# CONTROL_BOARD_V2.net
KiCad netlist of a schematic drawn in Altium Designer
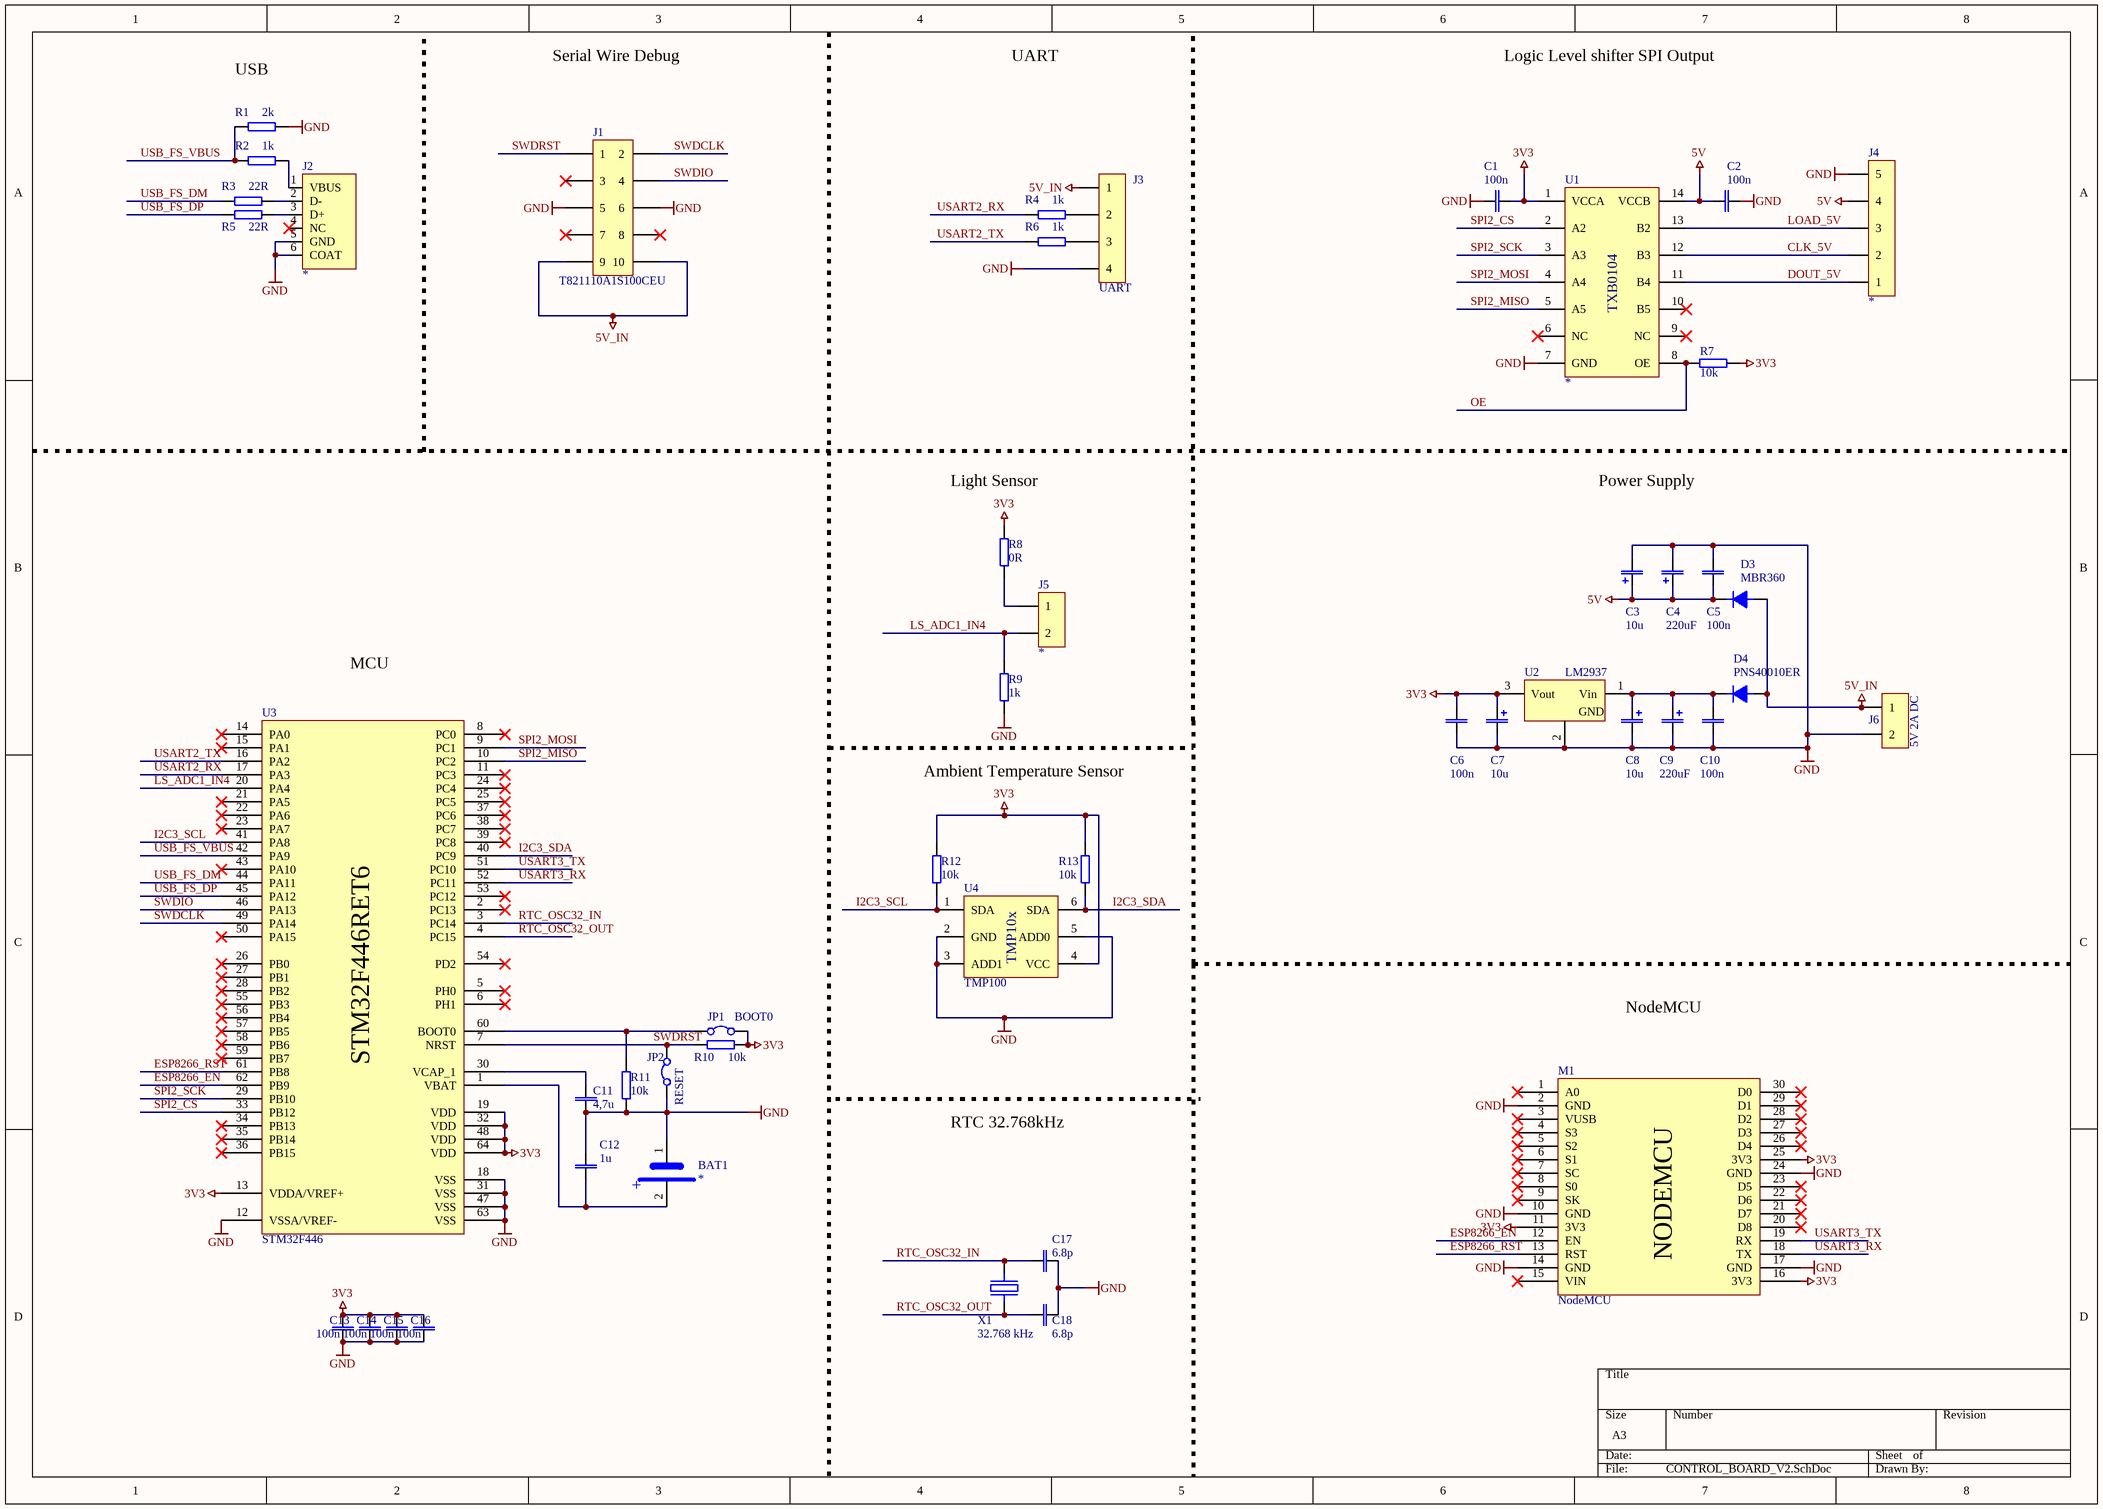
[diagram p0: CONTROL_BOARD_V2.SchDoc]

(export (version "E")
  (design (tool "Eeschema 10.0.6"))
  (components
    (comp (ref "BAT1")
      (value "*")
      (footprint "CR2032")
      (description "battery")
      (libsource (lib "SCH_LIB") (part "Battery"))
    )
    (comp (ref "C1")
      (value "100n")
      (footprint "CAP 0805")
      (description "NON POLARIZED CAPACITOR")
      (libsource (lib "SCH_LIB") (part "CAP"))
    )
    (comp (ref "C2")
      (value "100n")
      (footprint "CAP 0805")
      (description "NON POLARIZED CAPACITOR")
      (libsource (lib "SCH_LIB") (part "CAP"))
    )
    (comp (ref "C3")
      (value "10u")
      (footprint "CAP 1210")
      (description "POLARIZED CAPACITOR")
      (libsource (lib "SCH_LIB") (part "CAP_POL"))
    )
    (comp (ref "C4")
      (value "220uF")
      (footprint "G ELKO")
      (description "POLARIZED CAPACITOR")
      (libsource (lib "SCH_LIB") (part "CAP_POL"))
    )
    (comp (ref "C5")
      (value "100n")
      (footprint "CAP 0805")
      (description "NON POLARIZED CAPACITOR")
      (libsource (lib "SCH_LIB") (part "CAP"))
    )
    (comp (ref "C6")
      (value "100n")
      (footprint "CAP 0805")
      (description "NON POLARIZED CAPACITOR")
      (libsource (lib "SCH_LIB") (part "CAP"))
    )
    (comp (ref "C7")
      (value "10u")
      (footprint "CAP 1210")
      (description "POLARIZED CAPACITOR")
      (libsource (lib "SCH_LIB") (part "CAP_POL"))
    )
    (comp (ref "C8")
      (value "10u")
      (footprint "CAP 1210")
      (description "POLARIZED CAPACITOR")
      (libsource (lib "SCH_LIB") (part "CAP_POL"))
    )
    (comp (ref "C9")
      (value "220uF")
      (footprint "G ELKO")
      (description "POLARIZED CAPACITOR")
      (libsource (lib "SCH_LIB") (part "CAP_POL"))
    )
    (comp (ref "C10")
      (value "100n")
      (footprint "CAP 0805")
      (description "NON POLARIZED CAPACITOR")
      (libsource (lib "SCH_LIB") (part "CAP"))
    )
    (comp (ref "C11")
      (value "4,7u")
      (footprint "CAP 0805")
      (description "NON POLARIZED CAPACITOR")
      (libsource (lib "SCH_LIB") (part "CAP"))
    )
    (comp (ref "C12")
      (value "1u")
      (footprint "CAP 0805")
      (description "NON POLARIZED CAPACITOR")
      (libsource (lib "SCH_LIB") (part "CAP"))
    )
    (comp (ref "C13")
      (value "100n")
      (footprint "CAP 0805")
      (description "NON POLARIZED CAPACITOR")
      (libsource (lib "SCH_LIB") (part "CAP"))
    )
    (comp (ref "C14")
      (value "100n")
      (footprint "CAP 0805")
      (description "NON POLARIZED CAPACITOR")
      (libsource (lib "SCH_LIB") (part "CAP"))
    )
    (comp (ref "C15")
      (value "100n")
      (footprint "CAP 0805")
      (description "NON POLARIZED CAPACITOR")
      (libsource (lib "SCH_LIB") (part "CAP"))
    )
    (comp (ref "C16")
      (value "100n")
      (footprint "CAP 0805")
      (description "NON POLARIZED CAPACITOR")
      (libsource (lib "SCH_LIB") (part "CAP"))
    )
    (comp (ref "C17")
      (value "6.8p")
      (footprint "CAP 0805")
      (description "NON POLARIZED CAPACITOR")
      (libsource (lib "SCH_LIB") (part "CAP"))
    )
    (comp (ref "C18")
      (value "6.8p")
      (footprint "CAP 0805")
      (description "NON POLARIZED CAPACITOR")
      (libsource (lib "SCH_LIB") (part "CAP"))
    )
    (comp (ref "D3")
      (value "MBR360")
      (footprint "DO-201AD")
      (description "ON Semiconductor MBR360,SCHOTTKY BARRIER RECTIFIERS\r\n3.0 AMPERES 60 VOLTS")
      (fields (field (name "MANUFACTURER") "ON Semiconductor"))
      (libsource (lib "SCH_LIB") (part "MBR360"))
    )
    (comp (ref "D4")
      (value "PNS40010ER")
      (footprint "SOD-123")
      (description "Nexperia PNS40010ER,115 switching diode 1.4A, 400V, SOD-123")
      (fields (field (name "MANUFACTURER") "Nexperia"))
      (libsource (lib "SCH_LIB") (part "PNS40010ER"))
    )
    (comp (ref "J1")
      (value "T821110A1S100CEU")
      (footprint "MLW10")
      (description "T821, 10pin, 2x5 connector, 2.54mm")
      (fields (field (name "MANUFACTURER") "Amphenol"))
      (libsource (lib "SCH_LIB") (part "T821-10"))
    )
    (comp (ref "J2")
      (value "*")
      (footprint "MUSB-B2.0S05PFHSB-T")
      (description "5PIN miniUSB SMD connector")
      (libsource (lib "SCH_LIB") (part "USB_5PIN"))
    )
    (comp (ref "J3")
      (value "UART")
      (footprint "SIL4")
      (description "4 PIN HEADER")
      (libsource (lib "SCH_LIB") (part "HEADER4"))
    )
    (comp (ref "J4")
      (value "*")
      (footprint "SIL5")
      (description "5 PIN HEADER")
      (libsource (lib "SCH_LIB") (part "HEADER5"))
    )
    (comp (ref "J5")
      (value "*")
      (footprint "SIL2")
      (description "2 PIN HEADER")
      (libsource (lib "SCH_LIB") (part "HEADER2"))
    )
    (comp (ref "J6")
      (value "5V 2A DC")
      (footprint "PTR_AKZ350")
      (description "2 Pin Terminal Block")
      (fields (field (name "MANUFACTURER") "TE Connectivity"))
      (libsource (lib "SCH_LIB") (part "TB-2"))
    )
    (comp (ref "JP1")
      (value "BOOT0")
      (footprint "SIL2")
      (description "JUMPER")
      (libsource (lib "SCH_LIB") (part "JUMPER"))
    )
    (comp (ref "JP2")
      (value "RESET")
      (footprint "SIL2")
      (description "JUMPER")
      (libsource (lib "SCH_LIB") (part "JUMPER"))
    )
    (comp (ref "M1")
      (value "NodeMCU")
      (footprint "NodeMcu")
      (description "Node MCU ESP12 module")
      (libsource (lib "SCH_LIB") (part "NodeMCU"))
    )
    (comp (ref "R1")
      (value "2k")
      (footprint "RES 0805")
      (description "RESISTOR")
      (libsource (lib "SCH_LIB") (part "RES"))
    )
    (comp (ref "R2")
      (value "1k")
      (footprint "RES 0805")
      (description "RESISTOR")
      (libsource (lib "SCH_LIB") (part "RES"))
    )
    (comp (ref "R3")
      (value "22R")
      (footprint "RES 0805")
      (description "RESISTOR")
      (libsource (lib "SCH_LIB") (part "RES"))
    )
    (comp (ref "R4")
      (value "1k")
      (footprint "RES 0805")
      (description "RESISTOR")
      (libsource (lib "SCH_LIB") (part "RES"))
    )
    (comp (ref "R5")
      (value "22R")
      (footprint "RES 0805")
      (description "RESISTOR")
      (libsource (lib "SCH_LIB") (part "RES"))
    )
    (comp (ref "R6")
      (value "1k")
      (footprint "RES 0805")
      (description "RESISTOR")
      (libsource (lib "SCH_LIB") (part "RES"))
    )
    (comp (ref "R7")
      (value "10k")
      (footprint "RES 0805")
      (description "RESISTOR")
      (libsource (lib "SCH_LIB") (part "RES"))
    )
    (comp (ref "R8")
      (value "0R")
      (footprint "RES 0805")
      (description "RESISTOR")
      (libsource (lib "") (part "RES_2"))
    )
    (comp (ref "R9")
      (value "1k")
      (footprint "RES 0805")
      (description "RESISTOR")
      (libsource (lib "") (part "RES_2"))
    )
    (comp (ref "R10")
      (value "10k")
      (footprint "RES 0805")
      (description "RESISTOR")
      (libsource (lib "") (part "RES_3"))
    )
    (comp (ref "R11")
      (value "10k")
      (footprint "RES 0805")
      (description "RESISTOR")
      (libsource (lib "") (part "RES_1"))
    )
    (comp (ref "R12")
      (value "10k")
      (footprint "RES 0805")
      (description "RESISTOR")
      (libsource (lib "") (part "RES_1"))
    )
    (comp (ref "R13")
      (value "10k")
      (footprint "RES 0805")
      (description "RESISTOR")
      (libsource (lib "") (part "RES_1"))
    )
    (comp (ref "U1")
      (value "*")
      (footprint "SO14")
      (description "Voltage level shifter")
      (libsource (lib "SCH_LIB") (part "TXB0104"))
    )
    (comp (ref "U2")
      (value "LM2937")
      (footprint "SOT223")
      (description "LDO-regulator 400mA 3,3 V 5%, 4,75 → 26 V, SOT223")
      (fields (field (name "MANUFACTURER") "Texas Instruments"))
      (libsource (lib "SCH_LIB") (part "LM2937"))
    )
    (comp (ref "U3")
      (value "STM32F446")
      (footprint "LQFP64")
      (description "MCU STM32F446RET6 32bit, ARM Cortex M4, 180MHz, Flash, 128 kB RAM, 2xUSB USB, LQFP-64")
      (fields (field (name "MANUFACTURER") "ST Microelectronics"))
      (libsource (lib "SCH_LIB") (part "STM32F446RET6"))
    )
    (comp (ref "U4")
      (value "TMP100")
      (footprint "SOT-23-6L")
      (description "Temperature sensor with I2C interface")
      (fields (field (name "MANUFACTURER") "Texas Instruments"))
      (libsource (lib "SCH_LIB") (part "TMP10x"))
    )
    (comp (ref "X1")
      (value "32.768 kHz")
      (footprint "X32K768L104")
      (description "Crystal, 32.768 kHz, Cylinder Radial, 8mm x 3mm Dia, 12.5 pF, 20 ppm")
      (fields (field (name "MANUFACTURER") "AEL CRYSTALS"))
      (libsource (lib "SCH_LIB") (part "X32K768L104"))
    )
  )
  (nets
    (net (code "1") (name "/CLK_5V") (class "Default")
      (node (ref "J4") (pin "2") (pinfunction "2_2") (pintype "passive"))
      (node (ref "U1") (pin "12") (pinfunction "B3_12") (pintype "passive"))
    )
    (net (code "2") (name "/DOUT_5V") (class "Default")
      (node (ref "J4") (pin "1") (pinfunction "1_1") (pintype "passive"))
      (node (ref "U1") (pin "11") (pinfunction "B4_11") (pintype "passive"))
    )
    (net (code "3") (name "/ESP8266_EN") (class "Default")
      (node (ref "M1") (pin "12") (pinfunction "EN_12") (pintype "passive"))
      (node (ref "U3") (pin "62") (pinfunction "PB9_62") (pintype "passive"))
    )
    (net (code "4") (name "/ESP8266_RST") (class "Default")
      (node (ref "M1") (pin "13") (pinfunction "RST_13") (pintype "passive"))
      (node (ref "U3") (pin "61") (pinfunction "PB8_61") (pintype "passive"))
    )
    (net (code "5") (name "/I2C3_SCL") (class "Default")
      (node (ref "R12") (pin "1") (pinfunction "1_1") (pintype "passive"))
      (node (ref "U3") (pin "41") (pinfunction "PA8_41") (pintype "passive"))
      (node (ref "U4") (pin "1") (pinfunction "SDA_1") (pintype "passive"))
    )
    (net (code "6") (name "/I2C3_SDA") (class "Default")
      (node (ref "R13") (pin "1") (pinfunction "1_1") (pintype "passive"))
      (node (ref "U3") (pin "40") (pinfunction "PC9_40") (pintype "passive"))
      (node (ref "U4") (pin "6") (pinfunction "SDA_6") (pintype "passive"))
    )
    (net (code "7") (name "/LOAD_5V") (class "Default")
      (node (ref "J4") (pin "3") (pinfunction "3_3") (pintype "passive"))
      (node (ref "U1") (pin "13") (pinfunction "B2_13") (pintype "passive"))
    )
    (net (code "8") (name "/LS_ADC1_IN4") (class "Default")
      (node (ref "J5") (pin "2") (pinfunction "2_2") (pintype "passive"))
      (node (ref "R9") (pin "1") (pinfunction "1_1") (pintype "passive"))
      (node (ref "U3") (pin "20") (pinfunction "PA4_20") (pintype "passive"))
    )
    (net (code "9") (name "/OE") (class "Default")
      (node (ref "R7") (pin "2") (pinfunction "2_2") (pintype "passive"))
      (node (ref "U1") (pin "8") (pinfunction "OE_8") (pintype "passive"))
    )
    (net (code "10") (name "/RTC_OSC32_IN") (class "Default")
      (node (ref "C17") (pin "2") (pinfunction "2_2") (pintype "passive"))
      (node (ref "U3") (pin "3") (pinfunction "PC14_3") (pintype "passive"))
      (node (ref "X1") (pin "2") (pinfunction "GND_2") (pintype "passive"))
    )
    (net (code "11") (name "/RTC_OSC32_OUT") (class "Default")
      (node (ref "C18") (pin "2") (pinfunction "2_2") (pintype "passive"))
      (node (ref "U3") (pin "4") (pinfunction "PC15_4") (pintype "passive"))
      (node (ref "X1") (pin "1") (pinfunction "1_1") (pintype "passive"))
    )
    (net (code "12") (name "/SPI2_CS") (class "Default")
      (node (ref "U1") (pin "2") (pinfunction "A2_2") (pintype "passive"))
      (node (ref "U3") (pin "33") (pinfunction "PB12_33") (pintype "passive"))
    )
    (net (code "13") (name "/SPI2_MISO") (class "Default")
      (node (ref "U1") (pin "5") (pinfunction "A5_5") (pintype "passive"))
      (node (ref "U3") (pin "10") (pinfunction "PC2_10") (pintype "passive"))
    )
    (net (code "14") (name "/SPI2_MOSI") (class "Default")
      (node (ref "U1") (pin "4") (pinfunction "A4_4") (pintype "passive"))
      (node (ref "U3") (pin "9") (pinfunction "PC1_9") (pintype "passive"))
    )
    (net (code "15") (name "/SPI2_SCK") (class "Default")
      (node (ref "U1") (pin "3") (pinfunction "A3_3") (pintype "passive"))
      (node (ref "U3") (pin "29") (pinfunction "PB10_29") (pintype "passive"))
    )
    (net (code "16") (name "/SWDCLK") (class "Default")
      (node (ref "J1") (pin "2") (pinfunction "2_2") (pintype "passive"))
      (node (ref "U3") (pin "49") (pinfunction "PA14_49") (pintype "passive"))
    )
    (net (code "17") (name "/SWDIO") (class "Default")
      (node (ref "J1") (pin "4") (pinfunction "4_4") (pintype "passive"))
      (node (ref "U3") (pin "46") (pinfunction "PA13_46") (pintype "passive"))
    )
    (net (code "18") (name "/SWDRST") (class "Default")
      (node (ref "J1") (pin "1") (pinfunction "1_1") (pintype "passive"))
      (node (ref "JP2") (pin "2") (pinfunction "2_2") (pintype "passive"))
      (node (ref "R10") (pin "1") (pinfunction "1_1") (pintype "passive"))
      (node (ref "U3") (pin "7") (pinfunction "NRST_7") (pintype "passive"))
    )
    (net (code "19") (name "/USART2_RX") (class "Default")
      (node (ref "R4") (pin "2") (pinfunction "2_2") (pintype "passive"))
      (node (ref "U3") (pin "17") (pinfunction "PA3_17") (pintype "passive"))
    )
    (net (code "20") (name "/USART2_TX") (class "Default")
      (node (ref "R6") (pin "2") (pinfunction "2_2") (pintype "passive"))
      (node (ref "U3") (pin "16") (pinfunction "PA2_16") (pintype "passive"))
    )
    (net (code "21") (name "/USART3_RX") (class "Default")
      (node (ref "M1") (pin "18") (pinfunction "TX_18") (pintype "passive"))
      (node (ref "U3") (pin "52") (pinfunction "PC11_52") (pintype "passive"))
    )
    (net (code "22") (name "/USART3_TX") (class "Default")
      (node (ref "M1") (pin "19") (pinfunction "RX_19") (pintype "passive"))
      (node (ref "U3") (pin "51") (pinfunction "PC10_51") (pintype "passive"))
    )
    (net (code "23") (name "/USB_FS_DM") (class "Default")
      (node (ref "R3") (pin "2") (pinfunction "2_2") (pintype "passive"))
      (node (ref "U3") (pin "44") (pinfunction "PA11_44") (pintype "passive"))
    )
    (net (code "24") (name "/USB_FS_DP") (class "Default")
      (node (ref "R5") (pin "2") (pinfunction "2_2") (pintype "passive"))
      (node (ref "U3") (pin "45") (pinfunction "PA12_45") (pintype "passive"))
    )
    (net (code "25") (name "/USB_FS_VBUS") (class "Default")
      (node (ref "R1") (pin "2") (pinfunction "2_2") (pintype "passive"))
      (node (ref "R2") (pin "2") (pinfunction "2_2") (pintype "passive"))
      (node (ref "U3") (pin "42") (pinfunction "PA9_42") (pintype "passive"))
    )
    (net (code "26") (name "3V3") (class "Default")
      (node (ref "C1") (pin "2") (pinfunction "2_2") (pintype "passive"))
      (node (ref "C13") (pin "2") (pinfunction "2_2") (pintype "passive"))
      (node (ref "C14") (pin "2") (pinfunction "2_2") (pintype "passive"))
      (node (ref "C15") (pin "2") (pinfunction "2_2") (pintype "passive"))
      (node (ref "C16") (pin "2") (pinfunction "2_2") (pintype "passive"))
      (node (ref "C6") (pin "1") (pinfunction "1_1") (pintype "passive"))
      (node (ref "C7") (pin "1") (pinfunction "+_1") (pintype "passive"))
      (node (ref "JP1") (pin "2") (pinfunction "2_2") (pintype "passive"))
      (node (ref "M1") (pin "11") (pinfunction "3V3_11") (pintype "passive"))
      (node (ref "M1") (pin "16") (pinfunction "3V3_16") (pintype "passive"))
      (node (ref "M1") (pin "25") (pinfunction "3V3_25") (pintype "passive"))
      (node (ref "R10") (pin "2") (pinfunction "2_2") (pintype "passive"))
      (node (ref "R12") (pin "2") (pinfunction "2_2") (pintype "passive"))
      (node (ref "R13") (pin "2") (pinfunction "2_2") (pintype "passive"))
      (node (ref "R7") (pin "1") (pinfunction "1_1") (pintype "passive"))
      (node (ref "R8") (pin "1") (pinfunction "1_1") (pintype "passive"))
      (node (ref "U1") (pin "1") (pinfunction "VCCA_1") (pintype "passive"))
      (node (ref "U2") (pin "3") (pinfunction "Vout_3") (pintype "passive"))
      (node (ref "U3") (pin "13") (pinfunction "VDDA/VREF+_13") (pintype "passive"))
      (node (ref "U3") (pin "19") (pinfunction "VDD_19") (pintype "passive"))
      (node (ref "U3") (pin "32") (pinfunction "VDD_32") (pintype "passive"))
      (node (ref "U3") (pin "48") (pinfunction "VDD_48") (pintype "passive"))
      (node (ref "U3") (pin "64") (pinfunction "VDD_64") (pintype "passive"))
      (node (ref "U4") (pin "4") (pinfunction "VCC_4") (pintype "passive"))
    )
    (net (code "27") (name "5V") (class "Default")
      (node (ref "C2") (pin "1") (pinfunction "1_1") (pintype "passive"))
      (node (ref "C3") (pin "1") (pinfunction "+_1") (pintype "passive"))
      (node (ref "C4") (pin "1") (pinfunction "+_1") (pintype "passive"))
      (node (ref "C5") (pin "2") (pinfunction "2_2") (pintype "passive"))
      (node (ref "D3") (pin "2") (pinfunction "K_2") (pintype "passive"))
      (node (ref "J4") (pin "4") (pinfunction "4_4") (pintype "passive"))
      (node (ref "U1") (pin "14") (pinfunction "VCCB_14") (pintype "passive"))
    )
    (net (code "28") (name "5V_IN") (class "Default")
      (node (ref "D3") (pin "1") (pinfunction "A_1") (pintype "passive"))
      (node (ref "D4") (pin "1") (pinfunction "A_1") (pintype "passive"))
      (node (ref "J1") (pin "10") (pinfunction "10_10") (pintype "passive"))
      (node (ref "J1") (pin "9") (pinfunction "9_9") (pintype "passive"))
      (node (ref "J3") (pin "1") (pinfunction "1_1") (pintype "passive"))
      (node (ref "J6") (pin "1") (pinfunction "1_1") (pintype "passive"))
    )
    (net (code "29") (name "GND") (class "Default")
      (node (ref "BAT1") (pin "1") (pintype "passive"))
      (node (ref "C1") (pin "1") (pinfunction "1_1") (pintype "passive"))
      (node (ref "C10") (pin "2") (pinfunction "2_2") (pintype "passive"))
      (node (ref "C11") (pin "1") (pinfunction "1_1") (pintype "passive"))
      (node (ref "C12") (pin "1") (pinfunction "1_1") (pintype "passive"))
      (node (ref "C13") (pin "1") (pinfunction "1_1") (pintype "passive"))
      (node (ref "C14") (pin "1") (pinfunction "1_1") (pintype "passive"))
      (node (ref "C15") (pin "1") (pinfunction "1_1") (pintype "passive"))
      (node (ref "C16") (pin "1") (pinfunction "1_1") (pintype "passive"))
      (node (ref "C17") (pin "1") (pinfunction "1_1") (pintype "passive"))
      (node (ref "C18") (pin "1") (pinfunction "1_1") (pintype "passive"))
      (node (ref "C2") (pin "2") (pinfunction "2_2") (pintype "passive"))
      (node (ref "C3") (pin "2") (pinfunction "-_2") (pintype "passive"))
      (node (ref "C4") (pin "2") (pinfunction "-_2") (pintype "passive"))
      (node (ref "C5") (pin "1") (pinfunction "1_1") (pintype "passive"))
      (node (ref "C6") (pin "2") (pinfunction "2_2") (pintype "passive"))
      (node (ref "C7") (pin "2") (pinfunction "-_2") (pintype "passive"))
      (node (ref "C8") (pin "2") (pinfunction "-_2") (pintype "passive"))
      (node (ref "C9") (pin "2") (pinfunction "-_2") (pintype "passive"))
      (node (ref "J1") (pin "5") (pinfunction "5_5") (pintype "passive"))
      (node (ref "J1") (pin "6") (pinfunction "6_6") (pintype "passive"))
      (node (ref "J2") (pin "5") (pinfunction "GND_5") (pintype "passive"))
      (node (ref "J2") (pin "6") (pinfunction "COAT_6") (pintype "passive"))
      (node (ref "J3") (pin "4") (pinfunction "4_4") (pintype "passive"))
      (node (ref "J4") (pin "5") (pinfunction "5_5") (pintype "passive"))
      (node (ref "J6") (pin "2") (pinfunction "2_2") (pintype "passive"))
      (node (ref "JP2") (pin "1") (pinfunction "1_1") (pintype "passive"))
      (node (ref "M1") (pin "10") (pinfunction "GND_10") (pintype "passive"))
      (node (ref "M1") (pin "14") (pinfunction "GND_14") (pintype "passive"))
      (node (ref "M1") (pin "17") (pinfunction "GND_17") (pintype "passive"))
      (node (ref "M1") (pin "2") (pinfunction "GND_2") (pintype "passive"))
      (node (ref "M1") (pin "24") (pinfunction "GND_24") (pintype "passive"))
      (node (ref "R1") (pin "1") (pinfunction "1_1") (pintype "passive"))
      (node (ref "R11") (pin "1") (pinfunction "1_1") (pintype "passive"))
      (node (ref "R9") (pin "2") (pinfunction "2_2") (pintype "passive"))
      (node (ref "U1") (pin "7") (pinfunction "GND_7") (pintype "passive"))
      (node (ref "U2") (pin "2") (pinfunction "GND_2") (pintype "passive"))
      (node (ref "U3") (pin "12") (pinfunction "VSSA/VREF-_12") (pintype "passive"))
      (node (ref "U3") (pin "18") (pinfunction "VSS_18") (pintype "passive"))
      (node (ref "U3") (pin "31") (pinfunction "VSS_31") (pintype "passive"))
      (node (ref "U3") (pin "47") (pinfunction "VSS_47") (pintype "passive"))
      (node (ref "U3") (pin "63") (pinfunction "VSS_63") (pintype "passive"))
      (node (ref "U4") (pin "2") (pinfunction "GND_2") (pintype "passive"))
      (node (ref "U4") (pin "3") (pinfunction "ADD1_3") (pintype "passive"))
      (node (ref "U4") (pin "5") (pinfunction "ADD0_5") (pintype "passive"))
    )
    (net (code "30") (name "Net-(C8-+)") (class "Default")
      (node (ref "C10") (pin "1") (pinfunction "1_1") (pintype "passive"))
      (node (ref "C8") (pin "1") (pinfunction "+_1") (pintype "passive"))
      (node (ref "C9") (pin "1") (pinfunction "+_1") (pintype "passive"))
      (node (ref "D4") (pin "2") (pinfunction "K_2") (pintype "passive"))
      (node (ref "U2") (pin "1") (pinfunction "Vin_1") (pintype "passive"))
    )
    (net (code "31") (name "Net-(J2-D+)") (class "Default")
      (node (ref "J2") (pin "3") (pinfunction "D+_3") (pintype "passive"))
      (node (ref "R5") (pin "1") (pinfunction "1_1") (pintype "passive"))
    )
    (net (code "32") (name "Net-(J2-D-)") (class "Default")
      (node (ref "J2") (pin "2") (pinfunction "D-_2") (pintype "passive"))
      (node (ref "R3") (pin "1") (pinfunction "1_1") (pintype "passive"))
    )
    (net (code "33") (name "Net-(J2-VBUS)") (class "Default")
      (node (ref "J2") (pin "1") (pinfunction "VBUS_1") (pintype "passive"))
      (node (ref "R2") (pin "1") (pinfunction "1_1") (pintype "passive"))
    )
    (net (code "34") (name "Net-(J3-Pad2)") (class "Default")
      (node (ref "J3") (pin "2") (pinfunction "2_2") (pintype "passive"))
      (node (ref "R4") (pin "1") (pinfunction "1_1") (pintype "passive"))
    )
    (net (code "35") (name "Net-(J3-Pad3)") (class "Default")
      (node (ref "J3") (pin "3") (pinfunction "3_3") (pintype "passive"))
      (node (ref "R6") (pin "1") (pinfunction "1_1") (pintype "passive"))
    )
    (net (code "36") (name "Net-(J5-Pad1)") (class "Default")
      (node (ref "J5") (pin "1") (pinfunction "1_1") (pintype "passive"))
      (node (ref "R8") (pin "2") (pinfunction "2_2") (pintype "passive"))
    )
    (net (code "37") (name "Net-(U3-BOOT0)") (class "Default")
      (node (ref "JP1") (pin "1") (pinfunction "1_1") (pintype "passive"))
      (node (ref "R11") (pin "2") (pinfunction "2_2") (pintype "passive"))
      (node (ref "U3") (pin "60") (pinfunction "BOOT0_60") (pintype "passive"))
    )
    (net (code "38") (name "Net-(U3-VBAT)") (class "Default")
      (node (ref "BAT1") (pin "2") (pintype "passive"))
      (node (ref "C12") (pin "2") (pinfunction "2_2") (pintype "passive"))
      (node (ref "U3") (pin "1") (pinfunction "VBAT_1") (pintype "passive"))
    )
    (net (code "39") (name "Net-(U3-VCAP_1)") (class "Default")
      (node (ref "C11") (pin "2") (pinfunction "2_2") (pintype "passive"))
      (node (ref "U3") (pin "30") (pinfunction "VCAP_1_30") (pintype "passive"))
    )
    (net (code "40") (name "unconnected-(J1-Pad3)") (class "Default")
      (node (ref "J1") (pin "3") (pinfunction "3_3") (pintype "passive+no_connect"))
    )
    (net (code "41") (name "unconnected-(J1-Pad7)") (class "Default")
      (node (ref "J1") (pin "7") (pinfunction "7_7") (pintype "passive+no_connect"))
    )
    (net (code "42") (name "unconnected-(J1-Pad8)") (class "Default")
      (node (ref "J1") (pin "8") (pinfunction "8_8") (pintype "passive+no_connect"))
    )
    (net (code "43") (name "unconnected-(J2-NC-Pad4)") (class "Default")
      (node (ref "J2") (pin "4") (pinfunction "NC_4") (pintype "passive+no_connect"))
    )
    (net (code "44") (name "unconnected-(M1-A0-Pad1)") (class "Default")
      (node (ref "M1") (pin "1") (pinfunction "A0_1") (pintype "passive+no_connect"))
    )
    (net (code "45") (name "unconnected-(M1-D0-Pad30)") (class "Default")
      (node (ref "M1") (pin "30") (pinfunction "D0_30") (pintype "passive+no_connect"))
    )
    (net (code "46") (name "unconnected-(M1-D1-Pad29)") (class "Default")
      (node (ref "M1") (pin "29") (pinfunction "D1_29") (pintype "passive+no_connect"))
    )
    (net (code "47") (name "unconnected-(M1-D2-Pad28)") (class "Default")
      (node (ref "M1") (pin "28") (pinfunction "D2_28") (pintype "passive+no_connect"))
    )
    (net (code "48") (name "unconnected-(M1-D3-Pad27)") (class "Default")
      (node (ref "M1") (pin "27") (pinfunction "D3_27") (pintype "passive+no_connect"))
    )
    (net (code "49") (name "unconnected-(M1-D4-Pad26)") (class "Default")
      (node (ref "M1") (pin "26") (pinfunction "D4_26") (pintype "passive+no_connect"))
    )
    (net (code "50") (name "unconnected-(M1-D5-Pad23)") (class "Default")
      (node (ref "M1") (pin "23") (pinfunction "D5_23") (pintype "passive+no_connect"))
    )
    (net (code "51") (name "unconnected-(M1-D6-Pad22)") (class "Default")
      (node (ref "M1") (pin "22") (pinfunction "D6_22") (pintype "passive+no_connect"))
    )
    (net (code "52") (name "unconnected-(M1-D7-Pad21)") (class "Default")
      (node (ref "M1") (pin "21") (pinfunction "D7_21") (pintype "passive+no_connect"))
    )
    (net (code "53") (name "unconnected-(M1-D8-Pad20)") (class "Default")
      (node (ref "M1") (pin "20") (pinfunction "D8_20") (pintype "passive+no_connect"))
    )
    (net (code "54") (name "unconnected-(M1-S0-Pad8)") (class "Default")
      (node (ref "M1") (pin "8") (pinfunction "S0_8") (pintype "passive+no_connect"))
    )
    (net (code "55") (name "unconnected-(M1-S1-Pad6)") (class "Default")
      (node (ref "M1") (pin "6") (pinfunction "S1_6") (pintype "passive+no_connect"))
    )
    (net (code "56") (name "unconnected-(M1-S2-Pad5)") (class "Default")
      (node (ref "M1") (pin "5") (pinfunction "S2_5") (pintype "passive+no_connect"))
    )
    (net (code "57") (name "unconnected-(M1-S3-Pad4)") (class "Default")
      (node (ref "M1") (pin "4") (pinfunction "S3_4") (pintype "passive+no_connect"))
    )
    (net (code "58") (name "unconnected-(M1-SC-Pad7)") (class "Default")
      (node (ref "M1") (pin "7") (pinfunction "SC_7") (pintype "passive+no_connect"))
    )
    (net (code "59") (name "unconnected-(M1-SK-Pad9)") (class "Default")
      (node (ref "M1") (pin "9") (pinfunction "SK_9") (pintype "passive+no_connect"))
    )
    (net (code "60") (name "unconnected-(M1-VIN-Pad15)") (class "Default")
      (node (ref "M1") (pin "15") (pinfunction "VIN_15") (pintype "passive+no_connect"))
    )
    (net (code "61") (name "unconnected-(M1-VUSB-Pad3)") (class "Default")
      (node (ref "M1") (pin "3") (pinfunction "VUSB_3") (pintype "passive+no_connect"))
    )
    (net (code "62") (name "unconnected-(U1-B5-Pad10)") (class "Default")
      (node (ref "U1") (pin "10") (pinfunction "B5_10") (pintype "passive+no_connect"))
    )
    (net (code "63") (name "unconnected-(U1-NC-Pad6)") (class "Default")
      (node (ref "U1") (pin "6") (pinfunction "NC_6") (pintype "passive+no_connect"))
    )
    (net (code "64") (name "unconnected-(U1-NC-Pad9)") (class "Default")
      (node (ref "U1") (pin "9") (pinfunction "NC_9") (pintype "passive+no_connect"))
    )
    (net (code "65") (name "unconnected-(U3-PA0-Pad14)") (class "Default")
      (node (ref "U3") (pin "14") (pinfunction "PA0_14") (pintype "passive+no_connect"))
    )
    (net (code "66") (name "unconnected-(U3-PA1-Pad15)") (class "Default")
      (node (ref "U3") (pin "15") (pinfunction "PA1_15") (pintype "passive+no_connect"))
    )
    (net (code "67") (name "unconnected-(U3-PA5-Pad21)") (class "Default")
      (node (ref "U3") (pin "21") (pinfunction "PA5_21") (pintype "passive+no_connect"))
    )
    (net (code "68") (name "unconnected-(U3-PA6-Pad22)") (class "Default")
      (node (ref "U3") (pin "22") (pinfunction "PA6_22") (pintype "passive+no_connect"))
    )
    (net (code "69") (name "unconnected-(U3-PA7-Pad23)") (class "Default")
      (node (ref "U3") (pin "23") (pinfunction "PA7_23") (pintype "passive+no_connect"))
    )
    (net (code "70") (name "unconnected-(U3-PA10-Pad43)") (class "Default")
      (node (ref "U3") (pin "43") (pinfunction "PA10_43") (pintype "passive+no_connect"))
    )
    (net (code "71") (name "unconnected-(U3-PA15-Pad50)") (class "Default")
      (node (ref "U3") (pin "50") (pinfunction "PA15_50") (pintype "passive+no_connect"))
    )
    (net (code "72") (name "unconnected-(U3-PB0-Pad26)") (class "Default")
      (node (ref "U3") (pin "26") (pinfunction "PB0_26") (pintype "passive+no_connect"))
    )
    (net (code "73") (name "unconnected-(U3-PB1-Pad27)") (class "Default")
      (node (ref "U3") (pin "27") (pinfunction "PB1_27") (pintype "passive+no_connect"))
    )
    (net (code "74") (name "unconnected-(U3-PB2-Pad28)") (class "Default")
      (node (ref "U3") (pin "28") (pinfunction "PB2_28") (pintype "passive+no_connect"))
    )
    (net (code "75") (name "unconnected-(U3-PB3-Pad55)") (class "Default")
      (node (ref "U3") (pin "55") (pinfunction "PB3_55") (pintype "passive+no_connect"))
    )
    (net (code "76") (name "unconnected-(U3-PB4-Pad56)") (class "Default")
      (node (ref "U3") (pin "56") (pinfunction "PB4_56") (pintype "passive+no_connect"))
    )
    (net (code "77") (name "unconnected-(U3-PB5-Pad57)") (class "Default")
      (node (ref "U3") (pin "57") (pinfunction "PB5_57") (pintype "passive+no_connect"))
    )
    (net (code "78") (name "unconnected-(U3-PB6-Pad58)") (class "Default")
      (node (ref "U3") (pin "58") (pinfunction "PB6_58") (pintype "passive+no_connect"))
    )
    (net (code "79") (name "unconnected-(U3-PB7-Pad59)") (class "Default")
      (node (ref "U3") (pin "59") (pinfunction "PB7_59") (pintype "passive+no_connect"))
    )
    (net (code "80") (name "unconnected-(U3-PB13-Pad34)") (class "Default")
      (node (ref "U3") (pin "34") (pinfunction "PB13_34") (pintype "passive+no_connect"))
    )
    (net (code "81") (name "unconnected-(U3-PB14-Pad35)") (class "Default")
      (node (ref "U3") (pin "35") (pinfunction "PB14_35") (pintype "passive+no_connect"))
    )
    (net (code "82") (name "unconnected-(U3-PB15-Pad36)") (class "Default")
      (node (ref "U3") (pin "36") (pinfunction "PB15_36") (pintype "passive+no_connect"))
    )
    (net (code "83") (name "unconnected-(U3-PC0-Pad8)") (class "Default")
      (node (ref "U3") (pin "8") (pinfunction "PC0_8") (pintype "passive+no_connect"))
    )
    (net (code "84") (name "unconnected-(U3-PC3-Pad11)") (class "Default")
      (node (ref "U3") (pin "11") (pinfunction "PC3_11") (pintype "passive+no_connect"))
    )
    (net (code "85") (name "unconnected-(U3-PC4-Pad24)") (class "Default")
      (node (ref "U3") (pin "24") (pinfunction "PC4_24") (pintype "passive+no_connect"))
    )
    (net (code "86") (name "unconnected-(U3-PC5-Pad25)") (class "Default")
      (node (ref "U3") (pin "25") (pinfunction "PC5_25") (pintype "passive+no_connect"))
    )
    (net (code "87") (name "unconnected-(U3-PC6-Pad37)") (class "Default")
      (node (ref "U3") (pin "37") (pinfunction "PC6_37") (pintype "passive+no_connect"))
    )
    (net (code "88") (name "unconnected-(U3-PC7-Pad38)") (class "Default")
      (node (ref "U3") (pin "38") (pinfunction "PC7_38") (pintype "passive+no_connect"))
    )
    (net (code "89") (name "unconnected-(U3-PC8-Pad39)") (class "Default")
      (node (ref "U3") (pin "39") (pinfunction "PC8_39") (pintype "passive+no_connect"))
    )
    (net (code "90") (name "unconnected-(U3-PC12-Pad53)") (class "Default")
      (node (ref "U3") (pin "53") (pinfunction "PC12_53") (pintype "passive+no_connect"))
    )
    (net (code "91") (name "unconnected-(U3-PC13-Pad2)") (class "Default")
      (node (ref "U3") (pin "2") (pinfunction "PC13_2") (pintype "passive+no_connect"))
    )
    (net (code "92") (name "unconnected-(U3-PD2-Pad54)") (class "Default")
      (node (ref "U3") (pin "54") (pinfunction "PD2_54") (pintype "passive+no_connect"))
    )
    (net (code "93") (name "unconnected-(U3-PH0-Pad5)") (class "Default")
      (node (ref "U3") (pin "5") (pinfunction "PH0_5") (pintype "passive+no_connect"))
    )
    (net (code "94") (name "unconnected-(U3-PH1-Pad6)") (class "Default")
      (node (ref "U3") (pin "6") (pinfunction "PH1_6") (pintype "passive+no_connect"))
    )
  )
)
